# Decode.net
KiCad netlist of a schematic drawn in Altium Designer
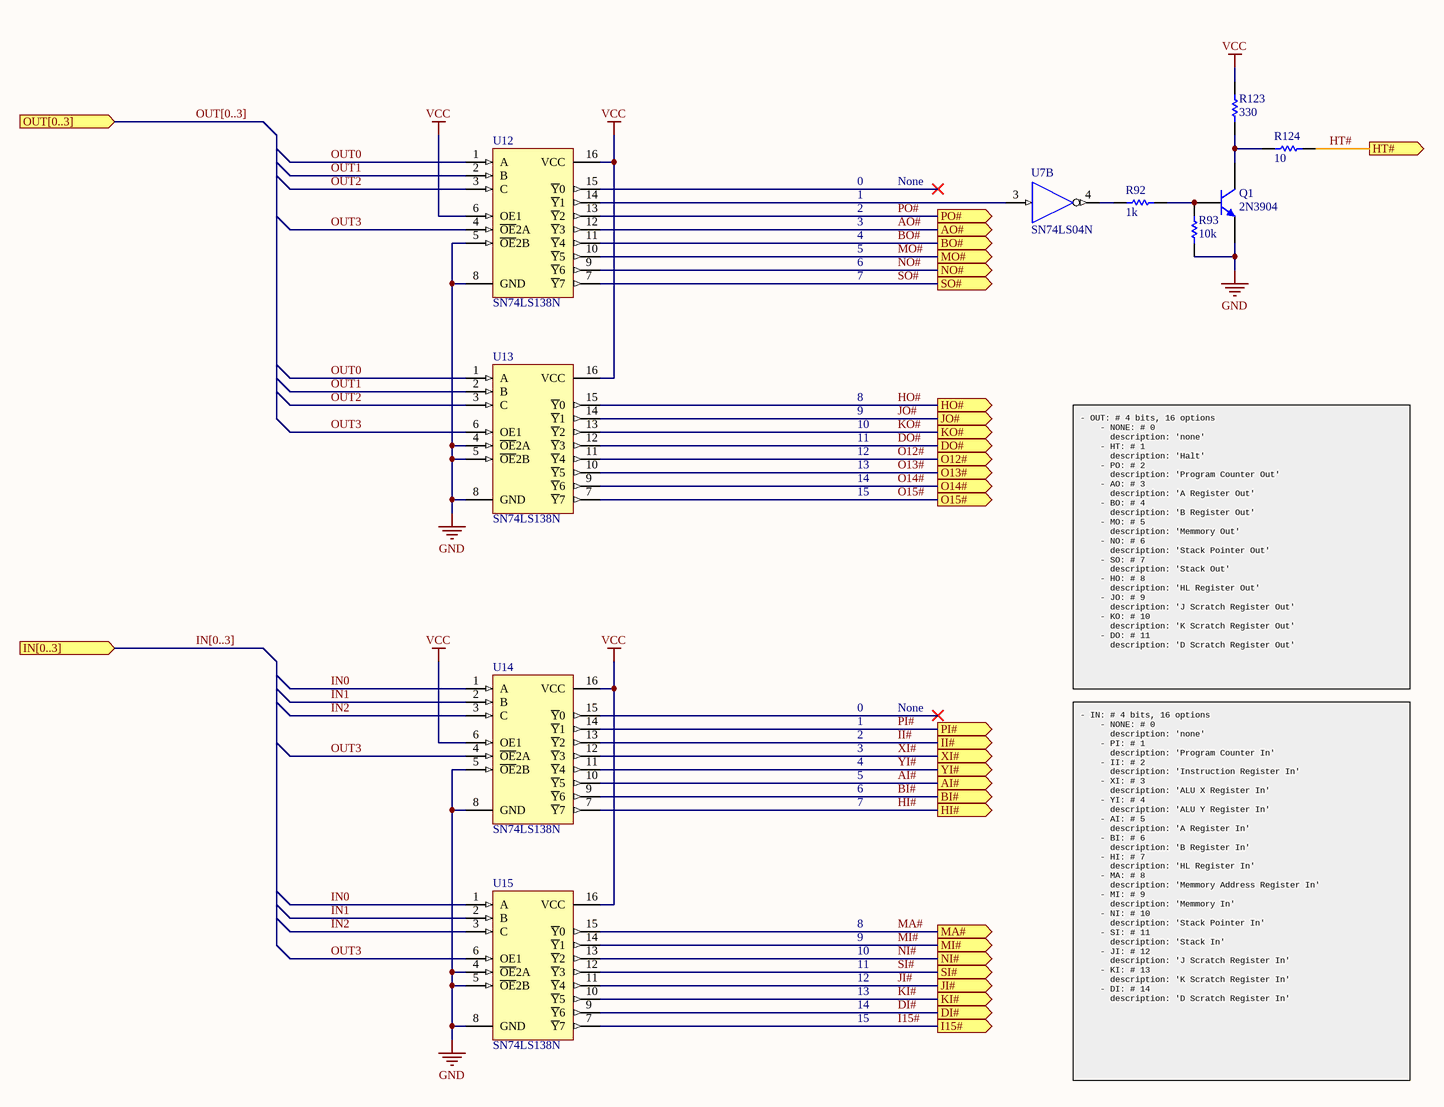
[diagram p0: Decode.SchDoc]

(export (version "E")
  (design (tool "Eeschema 10.0.6"))
  (components
    (comp (ref "Q1")
      (value "2N3904")
      (footprint "TO-92A")
      (description "NPN General Purpose Amplifier")
      (fields (field (name "PUBLISHER") "Altium Limited"))
      (libsource (lib "Miscellaneous Devices") (part "2N3904"))
    )
    (comp (ref "R92")
      (value "1k")
      (footprint "AXIAL-0.3")
      (description "Resistor")
      (fields (field (name "Comment") "Res1") (field (name "PUBLISHER") "Altium Limited"))
      (libsource (lib "Miscellaneous Devices") (part "Res1"))
    )
    (comp (ref "R93")
      (value "10k")
      (footprint "AXIAL-0.3")
      (description "Resistor")
      (fields (field (name "Comment") "Res1") (field (name "PUBLISHER") "Altium Limited"))
      (libsource (lib "Miscellaneous Devices") (part "Res1"))
    )
    (comp (ref "R123")
      (value "330")
      (footprint "AXIAL-0.3")
      (description "Resistor")
      (fields (field (name "Comment") "Res1") (field (name "PUBLISHER") "Altium Limited"))
      (libsource (lib "Miscellaneous Devices") (part "Res1"))
    )
    (comp (ref "R124")
      (value "10")
      (footprint "AXIAL-0.3")
      (description "Resistor")
      (fields (field (name "Comment") "Res1") (field (name "PUBLISHER") "Altium Limited"))
      (libsource (lib "Miscellaneous Devices") (part "Res1"))
    )
    (comp (ref "U7")
      (value "SN74LS04N")
      (footprint "N014")
      (description "Hex Inverter")
      (fields (field (name "PUBLISHER") "Altium Limited"))
      (libsource (lib "TI Logic Gate 2") (part "SN74LS04N"))
    )
    (comp (ref "U12")
      (value "SN74LS138N")
      (footprint "N016")
      (description "3-Line to 8-Line Decoder / Demultiplexer")
      (fields (field (name "PUBLISHER") "Altium Limited"))
      (libsource (lib "TI Logic Decoder Demux") (part "SN74LS138N"))
    )
    (comp (ref "U13")
      (value "SN74LS138N")
      (footprint "N016")
      (description "3-Line to 8-Line Decoder / Demultiplexer")
      (fields (field (name "PUBLISHER") "Altium Limited"))
      (libsource (lib "TI Logic Decoder Demux") (part "SN74LS138N"))
    )
    (comp (ref "U14")
      (value "SN74LS138N")
      (footprint "N016")
      (description "3-Line to 8-Line Decoder / Demultiplexer")
      (fields (field (name "PUBLISHER") "Altium Limited"))
      (libsource (lib "TI Logic Decoder Demux") (part "SN74LS138N"))
    )
    (comp (ref "U15")
      (value "SN74LS138N")
      (footprint "N016")
      (description "3-Line to 8-Line Decoder / Demultiplexer")
      (fields (field (name "PUBLISHER") "Altium Limited"))
      (libsource (lib "TI Logic Decoder Demux") (part "SN74LS138N"))
    )
  )
  (nets
    (net (code "2") (name "/AI#") (class "Default")
      (node (ref "U14") (pin "10") (pinfunction "~{Y}5_10") (pintype "output"))
    )
    (net (code "3") (name "/AO#") (class "Default")
      (node (ref "U12") (pin "12") (pinfunction "~{Y}3_12") (pintype "output"))
    )
    (net (code "4") (name "/BI#") (class "Default")
      (node (ref "U14") (pin "9") (pinfunction "~{Y}6_9") (pintype "output"))
    )
    (net (code "5") (name "/BO#") (class "Default")
      (node (ref "U12") (pin "11") (pinfunction "~{Y}4_11") (pintype "output"))
    )
    (net (code "6") (name "/DI#") (class "Default")
      (node (ref "U15") (pin "9") (pinfunction "~{Y}6_9") (pintype "output"))
    )
    (net (code "7") (name "/DO#") (class "Default")
      (node (ref "U13") (pin "12") (pinfunction "~{Y}3_12") (pintype "output"))
    )
    (net (code "8") (name "/HI#") (class "Default")
      (node (ref "U14") (pin "7") (pinfunction "~{Y}7_7") (pintype "output"))
    )
    (net (code "9") (name "/HO#") (class "Default")
      (node (ref "U13") (pin "15") (pinfunction "~{Y}0_15") (pintype "output"))
    )
    (net (code "10") (name "/HT#") (class "Default")
      (node (ref "R124") (pin "1") (pinfunction "1_1") (pintype "passive"))
    )
    (net (code "11") (name "/I15#") (class "Default")
      (node (ref "U15") (pin "7") (pinfunction "~{Y}7_7") (pintype "output"))
    )
    (net (code "12") (name "/II#") (class "Default")
      (node (ref "U14") (pin "13") (pinfunction "~{Y}2_13") (pintype "output"))
    )
    (net (code "13") (name "/IN0") (class "Default")
      (node (ref "U14") (pin "1") (pinfunction "A_1") (pintype "input"))
      (node (ref "U15") (pin "1") (pinfunction "A_1") (pintype "input"))
    )
    (net (code "14") (name "/IN1") (class "Default")
      (node (ref "U14") (pin "2") (pinfunction "B_2") (pintype "input"))
      (node (ref "U15") (pin "2") (pinfunction "B_2") (pintype "input"))
    )
    (net (code "15") (name "/IN2") (class "Default")
      (node (ref "U14") (pin "3") (pinfunction "C_3") (pintype "input"))
      (node (ref "U15") (pin "3") (pinfunction "C_3") (pintype "input"))
    )
    (net (code "17") (name "/JI#") (class "Default")
      (node (ref "U15") (pin "11") (pinfunction "~{Y}4_11") (pintype "output"))
    )
    (net (code "18") (name "/JO#") (class "Default")
      (node (ref "U13") (pin "14") (pinfunction "~{Y}1_14") (pintype "output"))
    )
    (net (code "19") (name "/KI#") (class "Default")
      (node (ref "U15") (pin "10") (pinfunction "~{Y}5_10") (pintype "output"))
    )
    (net (code "20") (name "/KO#") (class "Default")
      (node (ref "U13") (pin "13") (pinfunction "~{Y}2_13") (pintype "output"))
    )
    (net (code "21") (name "/MA#") (class "Default")
      (node (ref "U15") (pin "15") (pinfunction "~{Y}0_15") (pintype "output"))
    )
    (net (code "22") (name "/MI#") (class "Default")
      (node (ref "U15") (pin "14") (pinfunction "~{Y}1_14") (pintype "output"))
    )
    (net (code "23") (name "/MO#") (class "Default")
      (node (ref "U12") (pin "10") (pinfunction "~{Y}5_10") (pintype "output"))
    )
    (net (code "24") (name "/NI#") (class "Default")
      (node (ref "U15") (pin "13") (pinfunction "~{Y}2_13") (pintype "output"))
    )
    (net (code "25") (name "/NO#") (class "Default")
      (node (ref "U12") (pin "9") (pinfunction "~{Y}6_9") (pintype "output"))
    )
    (net (code "26") (name "/O12#") (class "Default")
      (node (ref "U13") (pin "11") (pinfunction "~{Y}4_11") (pintype "output"))
    )
    (net (code "27") (name "/O13#") (class "Default")
      (node (ref "U13") (pin "10") (pinfunction "~{Y}5_10") (pintype "output"))
    )
    (net (code "28") (name "/O14#") (class "Default")
      (node (ref "U13") (pin "9") (pinfunction "~{Y}6_9") (pintype "output"))
    )
    (net (code "29") (name "/O15#") (class "Default")
      (node (ref "U13") (pin "7") (pinfunction "~{Y}7_7") (pintype "output"))
    )
    (net (code "30") (name "/OUT0") (class "Default")
      (node (ref "U12") (pin "1") (pinfunction "A_1") (pintype "input"))
      (node (ref "U13") (pin "1") (pinfunction "A_1") (pintype "input"))
    )
    (net (code "31") (name "/OUT1") (class "Default")
      (node (ref "U12") (pin "2") (pinfunction "B_2") (pintype "input"))
      (node (ref "U13") (pin "2") (pinfunction "B_2") (pintype "input"))
    )
    (net (code "32") (name "/OUT2") (class "Default")
      (node (ref "U12") (pin "3") (pinfunction "C_3") (pintype "input"))
      (node (ref "U13") (pin "3") (pinfunction "C_3") (pintype "input"))
    )
    (net (code "33") (name "/OUT3") (class "Default")
      (node (ref "U12") (pin "4") (pinfunction "~{OE}2A_4") (pintype "input"))
      (node (ref "U13") (pin "6") (pinfunction "OE1_6") (pintype "input"))
      (node (ref "U14") (pin "4") (pinfunction "~{OE}2A_4") (pintype "input"))
      (node (ref "U15") (pin "6") (pinfunction "OE1_6") (pintype "input"))
    )
    (net (code "35") (name "/PI#") (class "Default")
      (node (ref "U14") (pin "14") (pinfunction "~{Y}1_14") (pintype "output"))
    )
    (net (code "36") (name "/PO#") (class "Default")
      (node (ref "U12") (pin "13") (pinfunction "~{Y}2_13") (pintype "output"))
    )
    (net (code "37") (name "/SI#") (class "Default")
      (node (ref "U15") (pin "12") (pinfunction "~{Y}3_12") (pintype "output"))
    )
    (net (code "38") (name "/SO#") (class "Default")
      (node (ref "U12") (pin "7") (pinfunction "~{Y}7_7") (pintype "output"))
    )
    (net (code "39") (name "/XI#") (class "Default")
      (node (ref "U14") (pin "12") (pinfunction "~{Y}3_12") (pintype "output"))
    )
    (net (code "40") (name "/YI#") (class "Default")
      (node (ref "U14") (pin "11") (pinfunction "~{Y}4_11") (pintype "output"))
    )
    (net (code "41") (name "GND") (class "Default")
      (node (ref "Q1") (pin "1") (pinfunction "E_1") (pintype "passive"))
      (node (ref "R93") (pin "2") (pinfunction "2_2") (pintype "passive"))
      (node (ref "U12") (pin "5") (pinfunction "~{OE}2B_5") (pintype "input"))
      (node (ref "U12") (pin "8") (pinfunction "GND_8") (pintype "power_in"))
      (node (ref "U13") (pin "4") (pinfunction "~{OE}2A_4") (pintype "input"))
      (node (ref "U13") (pin "5") (pinfunction "~{OE}2B_5") (pintype "input"))
      (node (ref "U13") (pin "8") (pinfunction "GND_8") (pintype "power_in"))
      (node (ref "U14") (pin "5") (pinfunction "~{OE}2B_5") (pintype "input"))
      (node (ref "U14") (pin "8") (pinfunction "GND_8") (pintype "power_in"))
      (node (ref "U15") (pin "4") (pinfunction "~{OE}2A_4") (pintype "input"))
      (node (ref "U15") (pin "5") (pinfunction "~{OE}2B_5") (pintype "input"))
      (node (ref "U15") (pin "8") (pinfunction "GND_8") (pintype "power_in"))
      (node (ref "U7") (pin "7") (pinfunction "GND_7") (pintype "power_in"))
    )
    (net (code "42") (name "Net-(Q1-B)") (class "Default")
      (node (ref "Q1") (pin "2") (pinfunction "B_2") (pintype "passive"))
      (node (ref "R92") (pin "1") (pinfunction "1_1") (pintype "passive"))
      (node (ref "R93") (pin "1") (pinfunction "1_1") (pintype "passive"))
    )
    (net (code "43") (name "Net-(Q1-C)") (class "Default")
      (node (ref "Q1") (pin "3") (pinfunction "C_3") (pintype "passive"))
      (node (ref "R123") (pin "2") (pinfunction "2_2") (pintype "passive"))
      (node (ref "R124") (pin "2") (pinfunction "2_2") (pintype "passive"))
    )
    (net (code "44") (name "Net-(U7B-Y)") (class "Default")
      (node (ref "R92") (pin "2") (pinfunction "2_2") (pintype "passive"))
      (node (ref "U7") (pin "4") (pinfunction "Y_4") (pintype "output"))
    )
    (net (code "45") (name "Net-(U12-~{Y}1)") (class "Default")
      (node (ref "U12") (pin "14") (pinfunction "~{Y}1_14") (pintype "output"))
      (node (ref "U7") (pin "3") (pinfunction "A_3") (pintype "input"))
    )
    (net (code "46") (name "VCC") (class "Default")
      (node (ref "R123") (pin "1") (pinfunction "1_1") (pintype "passive"))
      (node (ref "U12") (pin "16") (pinfunction "VCC_16") (pintype "power_in"))
      (node (ref "U12") (pin "6") (pinfunction "OE1_6") (pintype "input"))
      (node (ref "U13") (pin "16") (pinfunction "VCC_16") (pintype "power_in"))
      (node (ref "U14") (pin "16") (pinfunction "VCC_16") (pintype "power_in"))
      (node (ref "U14") (pin "6") (pinfunction "OE1_6") (pintype "input"))
      (node (ref "U15") (pin "16") (pinfunction "VCC_16") (pintype "power_in"))
      (node (ref "U7") (pin "14") (pinfunction "VCC_14") (pintype "power_in"))
    )
    (net (code "47") (name "unconnected-(U12-~{Y}0-Pad15)") (class "Default")
      (node (ref "U12") (pin "15") (pinfunction "~{Y}0_15") (pintype "output+no_connect"))
    )
    (net (code "48") (name "unconnected-(U14-~{Y}0-Pad15)") (class "Default")
      (node (ref "U14") (pin "15") (pinfunction "~{Y}0_15") (pintype "output+no_connect"))
    )
  )
)
